# mother_card_14.net
KiCad netlist of a schematic drawn in EAGLE
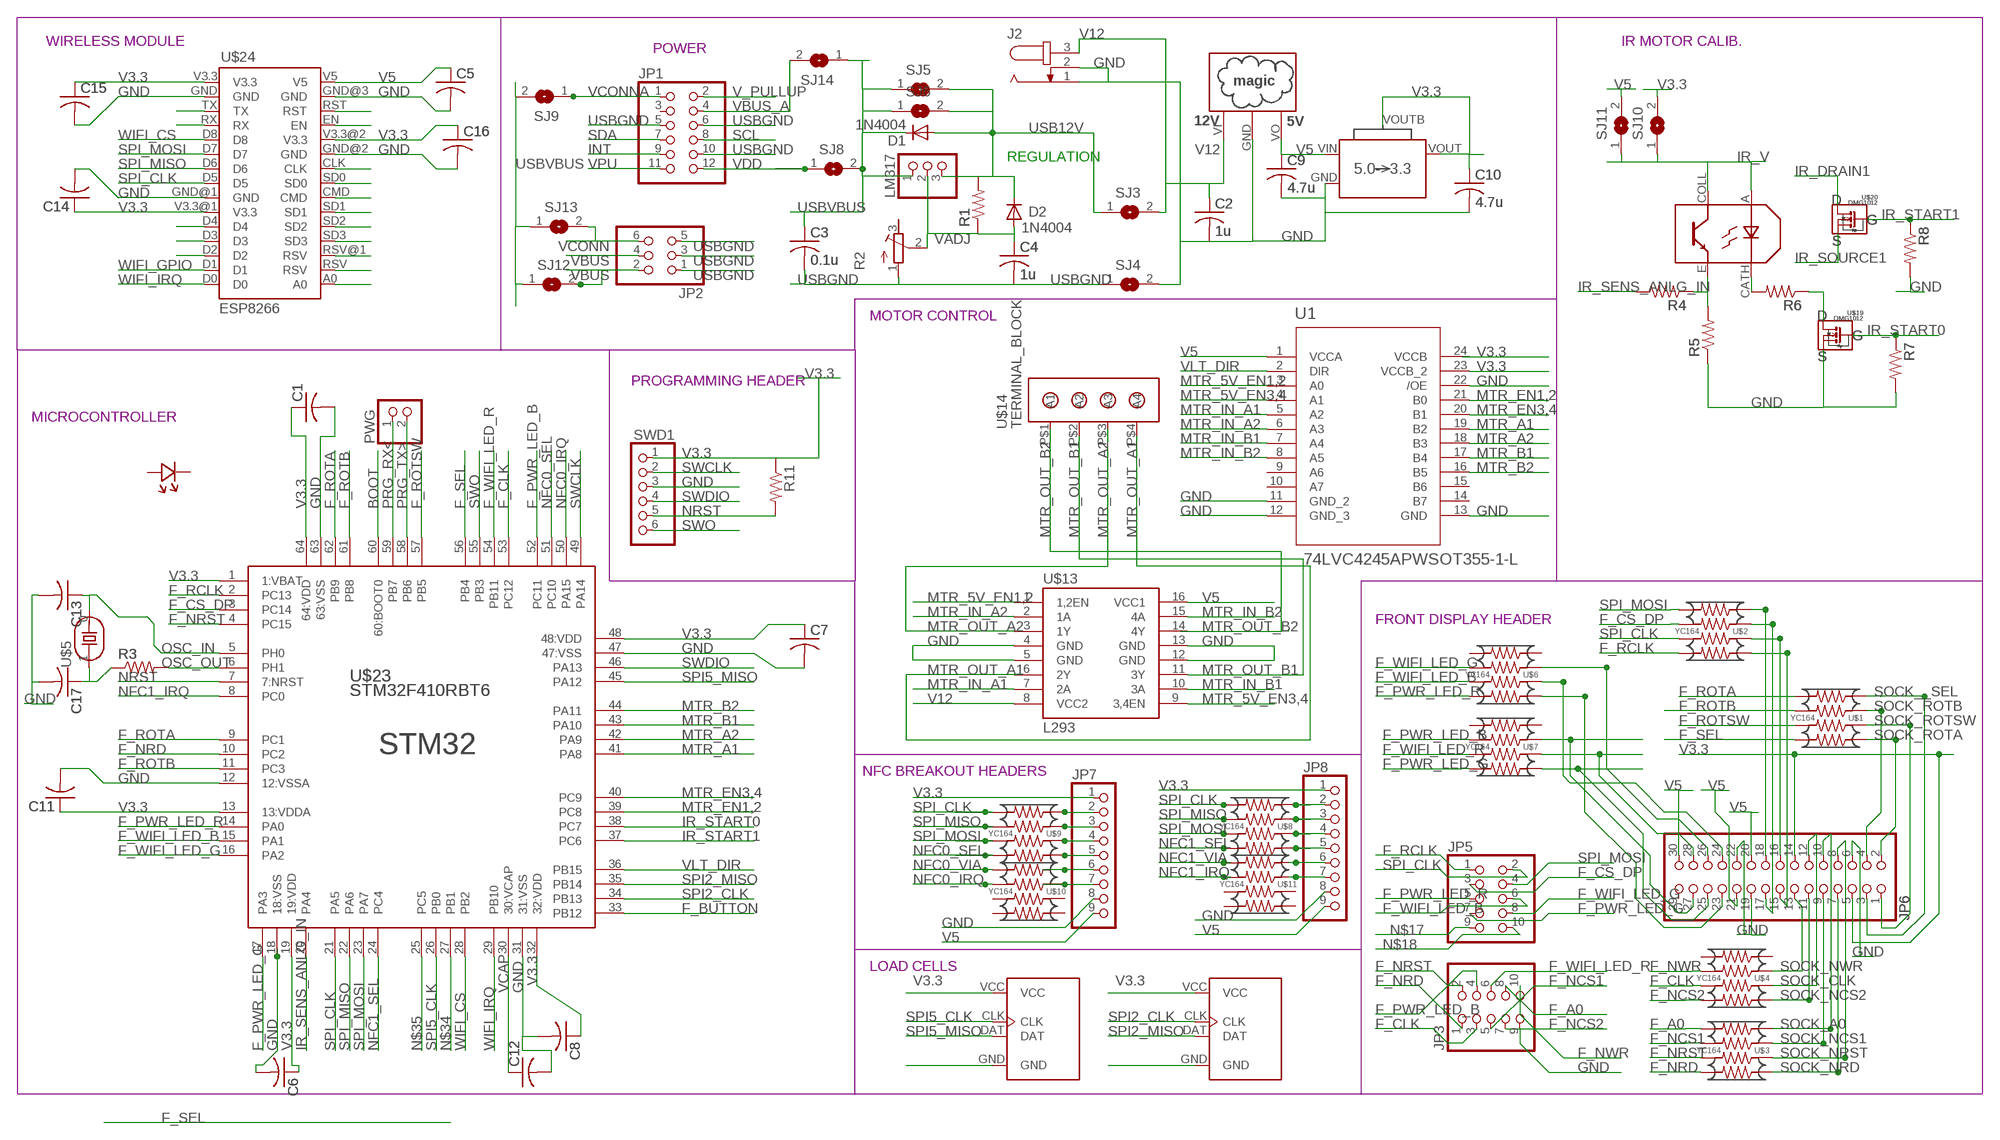
[diagram p0: schematic, sheet 1]

(export (version "E")
  (design (tool "Eeschema 10.0.6"))
  (components
    (comp (ref "C1")
      (value "C-USC0805")
      (footprint "eagle-import:C0805")
      (libsource (lib "eagle-import") (part "C-USC0805"))
    )
    (comp (ref "C2")
      (value "1u")
      (footprint "eagle-import:C0805")
      (libsource (lib "eagle-import") (part "C-USC0805"))
    )
    (comp (ref "C3")
      (value "0.1u")
      (footprint "eagle-import:C0805")
      (libsource (lib "eagle-import") (part "C-USC0805"))
    )
    (comp (ref "C4")
      (value "1u")
      (footprint "eagle-import:C0805")
      (libsource (lib "eagle-import") (part "C-USC0805"))
    )
    (comp (ref "C5")
      (value "C-USC0805")
      (footprint "eagle-import:C0805")
      (libsource (lib "eagle-import") (part "C-USC0805"))
    )
    (comp (ref "C6")
      (value "C-USC0805")
      (footprint "eagle-import:C0805")
      (libsource (lib "eagle-import") (part "C-USC0805"))
    )
    (comp (ref "C7")
      (value "C-USC0805")
      (footprint "eagle-import:C0805")
      (libsource (lib "eagle-import") (part "C-USC0805"))
    )
    (comp (ref "C8")
      (value "C-USC0805")
      (footprint "eagle-import:C0805")
      (libsource (lib "eagle-import") (part "C-USC0805"))
    )
    (comp (ref "C9")
      (value "4.7u")
      (footprint "eagle-import:C0805")
      (libsource (lib "eagle-import") (part "C-USC0805"))
    )
    (comp (ref "C10")
      (value "4.7u")
      (footprint "eagle-import:C0805")
      (libsource (lib "eagle-import") (part "C-USC0805"))
    )
    (comp (ref "C11")
      (value "C-USC0805")
      (footprint "eagle-import:C0805")
      (libsource (lib "eagle-import") (part "C-USC0805"))
    )
    (comp (ref "C12")
      (value "C-USC0805")
      (footprint "eagle-import:C0805")
      (libsource (lib "eagle-import") (part "C-USC0805"))
    )
    (comp (ref "C13")
      (value "C-USC0603")
      (footprint "eagle-import:C0603")
      (libsource (lib "eagle-import") (part "C-USC0603"))
    )
    (comp (ref "C14")
      (value "C-USC0805")
      (footprint "eagle-import:C0805")
      (libsource (lib "eagle-import") (part "C-USC0805"))
    )
    (comp (ref "C15")
      (value "C-USC0805")
      (footprint "eagle-import:C0805")
      (libsource (lib "eagle-import") (part "C-USC0805"))
    )
    (comp (ref "C16")
      (value "C-USC0805")
      (footprint "eagle-import:C0805")
      (libsource (lib "eagle-import") (part "C-USC0805"))
    )
    (comp (ref "C17")
      (value "C-USC0603")
      (footprint "eagle-import:C0603")
      (libsource (lib "eagle-import") (part "C-USC0603"))
    )
    (comp (ref "D1")
      (value "1N4004")
      (footprint "eagle-import:DO41-10")
      (libsource (lib "eagle-import") (part "1N4004"))
    )
    (comp (ref "D2")
      (value "1N4004")
      (footprint "eagle-import:DO41-10")
      (libsource (lib "eagle-import") (part "1N4004"))
    )
    (comp (ref "J2")
      (value "JACK-PLUG0")
      (footprint "eagle-import:SPC4077")
      (libsource (lib "eagle-import") (part "JACK-PLUG0"))
    )
    (comp (ref "JP1")
      (value "PINHD-2X6")
      (footprint "eagle-import:2X06")
      (libsource (lib "eagle-import") (part "PINHD-2X6"))
    )
    (comp (ref "JP2")
      (value "PINHD-2X3")
      (footprint "eagle-import:2X03")
      (libsource (lib "eagle-import") (part "PINHD-2X3"))
    )
    (comp (ref "JP3")
      (value "PINHD-2X5")
      (footprint "eagle-import:2X05")
      (libsource (lib "eagle-import") (part "PINHD-2X5"))
    )
    (comp (ref "JP5")
      (value "PINHD-2X5")
      (footprint "eagle-import:2X05")
      (libsource (lib "eagle-import") (part "PINHD-2X5"))
    )
    (comp (ref "JP6")
      (value "PINHD-2X15/SOCK")
      (footprint "eagle-import:2X15_SOCK")
      (libsource (lib "eagle-import") (part "PINHD-2X15/SOCK"))
    )
    (comp (ref "JP7")
      (value "PINHD-1X9/90")
      (footprint "eagle-import:1X09_90")
      (libsource (lib "eagle-import") (part "PINHD-1X9/90"))
    )
    (comp (ref "JP8")
      (value "PINHD-1X9/90")
      (footprint "eagle-import:1X09_90")
      (libsource (lib "eagle-import") (part "PINHD-1X9/90"))
    )
    (comp (ref "LM317")
      (value "PINHD-1X3")
      (footprint "eagle-import:1X03")
      (libsource (lib "eagle-import") (part "PINHD-1X3"))
    )
    (comp (ref "PWG")
      (value "PINHD-1X2")
      (footprint "eagle-import:1X02")
      (libsource (lib "eagle-import") (part "PINHD-1X2"))
    )
    (comp (ref "R1")
      (value "R-US_R0805")
      (footprint "eagle-import:R0805")
      (libsource (lib "eagle-import") (part "seniorDesign_R-US_R0805"))
    )
    (comp (ref "R2")
      (value "R-TRIMM64W")
      (footprint "eagle-import:RTRIM64W")
      (libsource (lib "eagle-import") (part "R-TRIMM64W"))
    )
    (comp (ref "R3")
      (value "R-US_R0805")
      (footprint "eagle-import:R0805")
      (libsource (lib "eagle-import") (part "seniorDesign_R-US_R0805"))
    )
    (comp (ref "R4")
      (value "R-US_R0805")
      (footprint "eagle-import:R0805")
      (libsource (lib "eagle-import") (part "seniorDesign_R-US_R0805"))
    )
    (comp (ref "R5")
      (value "R-US_R0805")
      (footprint "eagle-import:R0805")
      (libsource (lib "eagle-import") (part "seniorDesign_R-US_R0805"))
    )
    (comp (ref "R6")
      (value "R-US_R0805")
      (footprint "eagle-import:R0805")
      (libsource (lib "eagle-import") (part "seniorDesign_R-US_R0805"))
    )
    (comp (ref "R7")
      (value "R-US_R0805")
      (footprint "eagle-import:R0805")
      (libsource (lib "eagle-import") (part "seniorDesign_R-US_R0805"))
    )
    (comp (ref "R8")
      (value "R-US_R0805")
      (footprint "eagle-import:R0805")
      (libsource (lib "eagle-import") (part "seniorDesign_R-US_R0805"))
    )
    (comp (ref "R11")
      (value "R-US_R0805")
      (footprint "eagle-import:R0805")
      (libsource (lib "eagle-import") (part "R-US_R0805"))
    )
    (comp (ref "SJ3") (value "SJ") (footprint "eagle-import:SJ") (libsource (lib "eagle-import") (part "SJ")))
    (comp (ref "SJ4") (value "SJ") (footprint "eagle-import:SJ") (libsource (lib "eagle-import") (part "SJ")))
    (comp (ref "SJ5") (value "SJ") (footprint "eagle-import:SJ") (libsource (lib "eagle-import") (part "SJ")))
    (comp (ref "SJ6") (value "SJ") (footprint "eagle-import:SJ") (libsource (lib "eagle-import") (part "SJ")))
    (comp (ref "SJ8") (value "SJ") (footprint "eagle-import:SJ") (libsource (lib "eagle-import") (part "SJ")))
    (comp (ref "SJ9") (value "SJ") (footprint "eagle-import:SJ") (libsource (lib "eagle-import") (part "SJ")))
    (comp (ref "SJ10")
      (value "SJ")
      (footprint "eagle-import:SJ")
      (libsource (lib "eagle-import") (part "SJ"))
    )
    (comp (ref "SJ11")
      (value "SJ")
      (footprint "eagle-import:SJ")
      (libsource (lib "eagle-import") (part "SJ"))
    )
    (comp (ref "SJ12")
      (value "SJ")
      (footprint "eagle-import:SJ")
      (libsource (lib "eagle-import") (part "SJ"))
    )
    (comp (ref "SJ13")
      (value "SJ")
      (footprint "eagle-import:SJ")
      (libsource (lib "eagle-import") (part "SJ"))
    )
    (comp (ref "SJ14")
      (value "SJ")
      (footprint "eagle-import:SJ")
      (libsource (lib "eagle-import") (part "SJ"))
    )
    (comp (ref "SWD1")
      (value "PINHD-1X6")
      (footprint "eagle-import:1X06")
      (libsource (lib "eagle-import") (part "PINHD-1X6"))
    )
    (comp (ref "U$1")
      (value "YC164")
      (footprint "eagle-import:YC164")
      (libsource (lib "eagle-import") (part "YC164"))
    )
    (comp (ref "U$2")
      (value "YC164")
      (footprint "eagle-import:YC164")
      (libsource (lib "eagle-import") (part "YC164"))
    )
    (comp (ref "U$3")
      (value "YC164")
      (footprint "eagle-import:YC164")
      (libsource (lib "eagle-import") (part "YC164"))
    )
    (comp (ref "U$4")
      (value "YC164")
      (footprint "eagle-import:YC164")
      (libsource (lib "eagle-import") (part "YC164"))
    )
    (comp (ref "U$5")
      (value "HC-49S_9B")
      (footprint "eagle-import:HC-49S_9B")
      (libsource (lib "eagle-import") (part "HC-49S_9B"))
    )
    (comp (ref "U$6")
      (value "YC164")
      (footprint "eagle-import:YC164")
      (libsource (lib "eagle-import") (part "YC164"))
    )
    (comp (ref "U$7")
      (value "YC164")
      (footprint "eagle-import:YC164")
      (libsource (lib "eagle-import") (part "YC164"))
    )
    (comp (ref "U$8")
      (value "YC164")
      (footprint "eagle-import:YC164")
      (libsource (lib "eagle-import") (part "YC164"))
    )
    (comp (ref "U$9")
      (value "YC164")
      (footprint "eagle-import:YC164")
      (libsource (lib "eagle-import") (part "YC164"))
    )
    (comp (ref "U$10")
      (value "YC164")
      (footprint "eagle-import:YC164")
      (libsource (lib "eagle-import") (part "YC164"))
    )
    (comp (ref "U$11")
      (value "YC164")
      (footprint "eagle-import:YC164")
      (libsource (lib "eagle-import") (part "YC164"))
    )
    (comp (ref "U$12")
      (value "LED0603")
      (footprint "eagle-import:LED")
      (libsource (lib "eagle-import") (part "LED0603"))
    )
    (comp (ref "U$13")
      (value "L293")
      (footprint "eagle-import:DIL16")
      (libsource (lib "eagle-import") (part "L293"))
    )
    (comp (ref "U$14")
      (value "TERMINAL_BLOCK")
      (footprint "eagle-import:1X4_BLOCK")
      (libsource (lib "eagle-import") (part "TERMINAL_BLOCK"))
    )
    (comp (ref "U$15")
      (value "AP2114H")
      (footprint "eagle-import:AP2114H")
      (libsource (lib "eagle-import") (part "AP2114H"))
    )
    (comp (ref "U$16")
      (value "OKI-78SR-W36")
      (footprint "eagle-import:SIP3")
      (libsource (lib "eagle-import") (part "OKI-78SR-W36"))
    )
    (comp (ref "U$18")
      (value "TCRT5000")
      (footprint "eagle-import:TCRT5000")
      (libsource (lib "eagle-import") (part "TCRT5000"))
    )
    (comp (ref "U$19")
      (value "DMG1012")
      (footprint "eagle-import:SOT323")
      (libsource (lib "eagle-import") (part "DMG1012"))
    )
    (comp (ref "U$20")
      (value "DMG1012")
      (footprint "eagle-import:SOT323")
      (libsource (lib "eagle-import") (part "DMG1012"))
    )
    (comp (ref "U$21")
      (value "HX711")
      (footprint "eagle-import:HX711")
      (libsource (lib "eagle-import") (part "HX711"))
    )
    (comp (ref "U$22")
      (value "HX711")
      (footprint "eagle-import:HX711")
      (libsource (lib "eagle-import") (part "HX711"))
    )
    (comp (ref "U$23")
      (value "STM32F410RBT6")
      (footprint "eagle-import:QFP50P1200X1200X160-64N")
      (libsource (lib "eagle-import") (part "STM32F410RBT6"))
    )
    (comp (ref "U$24")
      (value "ESP8266")
      (footprint "eagle-import:ESP8266")
      (libsource (lib "eagle-import") (part "ESP8266"))
    )
    (comp (ref "U1")
      (value "74LVC4245APWSOT355-1-L")
      (footprint "eagle-import:SOT355-1-L")
      (fields (field (name "MANUFACTURER_PART_NUMBER") "74LVC4245APW"))
      (libsource (lib "eagle-import") (part "74LVC4245APWSOT355-1-L"))
    )
  )
  (nets
    (net (code "1") (name "/BOOT") (class "Default")
      (node (ref "U$23") (pin "60") (pinfunction "60:BOOT0_60") (pintype "bidirectional"))
    )
    (net (code "2") (name "/F_A0") (class "Default")
      (node (ref "JP3") (pin "8") (pinfunction "8_8") (pintype "passive"))
      (node (ref "U$3") (pin "P$4") (pinfunction "4_P$4") (pintype "passive"))
    )
    (net (code "3") (name "/F_BUTTON") (class "Default")
      (node (ref "U$23") (pin "33") (pinfunction "PB12_33") (pintype "bidirectional"))
    )
    (net (code "4") (name "/F_CLK") (class "Default")
      (node (ref "JP3") (pin "3") (pinfunction "3_3") (pintype "passive"))
      (node (ref "U$23") (pin "53") (pinfunction "PC12_53") (pintype "bidirectional"))
      (node (ref "U$4") (pin "P$2") (pinfunction "2_P$2") (pintype "passive"))
    )
    (net (code "5") (name "/F_CS_DP") (class "Default")
      (node (ref "JP5") (pin "3") (pinfunction "3_3") (pintype "passive"))
      (node (ref "U$2") (pin "P$3") (pinfunction "3_P$3") (pintype "passive"))
      (node (ref "U$23") (pin "3") (pinfunction "PC14_3") (pintype "bidirectional"))
    )
    (net (code "6") (name "/F_NCS1") (class "Default")
      (node (ref "JP3") (pin "5") (pinfunction "5_5") (pintype "passive"))
      (node (ref "U$3") (pin "P$3") (pinfunction "3_P$3") (pintype "passive"))
    )
    (net (code "7") (name "/F_NCS2") (class "Default")
      (node (ref "JP3") (pin "7") (pinfunction "7_7") (pintype "passive"))
      (node (ref "U$4") (pin "P$1") (pinfunction "1_P$1") (pintype "passive"))
    )
    (net (code "8") (name "/F_NRD") (class "Default")
      (node (ref "JP3") (pin "1") (pinfunction "1_1") (pintype "passive"))
      (node (ref "U$23") (pin "10") (pinfunction "PC2_10") (pintype "bidirectional"))
      (node (ref "U$3") (pin "P$1") (pinfunction "1_P$1") (pintype "passive"))
    )
    (net (code "9") (name "/F_NRST") (class "Default")
      (node (ref "JP3") (pin "2") (pinfunction "2_2") (pintype "passive"))
      (node (ref "U$23") (pin "4") (pinfunction "PC15_4") (pintype "bidirectional"))
      (node (ref "U$3") (pin "P$2") (pinfunction "2_P$2") (pintype "passive"))
    )
    (net (code "10") (name "/F_NWR") (class "Default")
      (node (ref "JP3") (pin "10") (pinfunction "10_10") (pintype "passive"))
      (node (ref "U$4") (pin "P$3") (pinfunction "3_P$3") (pintype "passive"))
    )
    (net (code "11") (name "/F_PWR_LED_B") (class "Default")
      (node (ref "JP3") (pin "4") (pinfunction "4_4") (pintype "passive"))
      (node (ref "U$23") (pin "52") (pinfunction "PC11_52") (pintype "bidirectional"))
      (node (ref "U$7") (pin "P$3") (pinfunction "3_P$3") (pintype "passive"))
    )
    (net (code "12") (name "/F_PWR_LED_G") (class "Default")
      (node (ref "JP5") (pin "7") (pinfunction "7_7") (pintype "passive"))
      (node (ref "U$23") (pin "17") (pinfunction "PA3_17") (pintype "bidirectional"))
      (node (ref "U$7") (pin "P$1") (pinfunction "1_P$1") (pintype "passive"))
    )
    (net (code "13") (name "/F_PWR_LED_R") (class "Default")
      (node (ref "JP5") (pin "5") (pinfunction "5_5") (pintype "passive"))
      (node (ref "U$23") (pin "14") (pinfunction "PA0_14") (pintype "bidirectional"))
      (node (ref "U$6") (pin "P$1") (pinfunction "1_P$1") (pintype "passive"))
    )
    (net (code "14") (name "/F_RCLK") (class "Default")
      (node (ref "JP5") (pin "1") (pinfunction "1_1") (pintype "passive"))
      (node (ref "U$2") (pin "P$1") (pinfunction "1_P$1") (pintype "passive"))
      (node (ref "U$23") (pin "2") (pinfunction "PC13_2") (pintype "bidirectional"))
    )
    (net (code "15") (name "/F_ROTA") (class "Default")
      (node (ref "U$1") (pin "P$4") (pinfunction "4_P$4") (pintype "passive"))
      (node (ref "U$23") (pin "62") (pinfunction "PB9_62") (pintype "bidirectional"))
      (node (ref "U$23") (pin "9") (pinfunction "PC1_9") (pintype "bidirectional"))
    )
    (net (code "16") (name "/F_ROTB") (class "Default")
      (node (ref "U$1") (pin "P$3") (pinfunction "3_P$3") (pintype "passive"))
      (node (ref "U$23") (pin "11") (pinfunction "PC3_11") (pintype "bidirectional"))
      (node (ref "U$23") (pin "61") (pinfunction "PB8_61") (pintype "bidirectional"))
    )
    (net (code "17") (name "/F_ROTSW") (class "Default")
      (node (ref "U$1") (pin "P$2") (pinfunction "2_P$2") (pintype "passive"))
      (node (ref "U$23") (pin "57") (pinfunction "PB5_57") (pintype "bidirectional"))
    )
    (net (code "18") (name "/F_SEL") (class "Default")
      (node (ref "U$1") (pin "P$1") (pinfunction "1_P$1") (pintype "passive"))
      (node (ref "U$23") (pin "56") (pinfunction "PB4_56") (pintype "bidirectional"))
    )
    (net (code "19") (name "/F_WIFI_LED_B") (class "Default")
      (node (ref "JP5") (pin "6") (pinfunction "6_6") (pintype "passive"))
      (node (ref "U$23") (pin "15") (pinfunction "PA1_15") (pintype "bidirectional"))
      (node (ref "U$6") (pin "P$2") (pinfunction "2_P$2") (pintype "passive"))
    )
    (net (code "20") (name "/F_WIFI_LED_G") (class "Default")
      (node (ref "JP5") (pin "8") (pinfunction "8_8") (pintype "passive"))
      (node (ref "U$23") (pin "16") (pinfunction "PA2_16") (pintype "bidirectional"))
      (node (ref "U$6") (pin "P$3") (pinfunction "3_P$3") (pintype "passive"))
    )
    (net (code "21") (name "/F_WIFI_LED_R") (class "Default")
      (node (ref "JP3") (pin "6") (pinfunction "6_6") (pintype "passive"))
      (node (ref "U$23") (pin "54") (pinfunction "PB11_54") (pintype "bidirectional"))
      (node (ref "U$7") (pin "P$2") (pinfunction "2_P$2") (pintype "passive"))
    )
    (net (code "22") (name "/GND") (class "Default")
      (node (ref "C1") (pin "2") (pinfunction "2_2") (pintype "passive"))
      (node (ref "C10") (pin "2") (pinfunction "2_2") (pintype "passive"))
      (node (ref "C11") (pin "2") (pinfunction "2_2") (pintype "passive"))
      (node (ref "C12") (pin "2") (pinfunction "2_2") (pintype "passive"))
      (node (ref "C13") (pin "2") (pinfunction "2_2") (pintype "passive"))
      (node (ref "C14") (pin "2") (pinfunction "2_2") (pintype "passive"))
      (node (ref "C15") (pin "2") (pinfunction "2_2") (pintype "passive"))
      (node (ref "C16") (pin "2") (pinfunction "2_2") (pintype "passive"))
      (node (ref "C17") (pin "2") (pinfunction "2_2") (pintype "passive"))
      (node (ref "C2") (pin "2") (pinfunction "2_2") (pintype "passive"))
      (node (ref "C5") (pin "2") (pinfunction "2_2") (pintype "passive"))
      (node (ref "C6") (pin "2") (pinfunction "2_2") (pintype "passive"))
      (node (ref "C7") (pin "2") (pinfunction "2_2") (pintype "passive"))
      (node (ref "C8") (pin "2") (pinfunction "2_2") (pintype "passive"))
      (node (ref "C9") (pin "2") (pinfunction "2_2") (pintype "passive"))
      (node (ref "J2") (pin "1") (pinfunction "1_1") (pintype "passive"))
      (node (ref "J2") (pin "2") (pinfunction "2_2") (pintype "passive"))
      (node (ref "JP3") (pin "9") (pinfunction "9_9") (pintype "passive"))
      (node (ref "JP6") (pin "19") (pinfunction "19_19") (pintype "passive"))
      (node (ref "JP6") (pin "22") (pinfunction "22_22") (pintype "passive"))
      (node (ref "JP6") (pin "6") (pinfunction "6_6") (pintype "passive"))
      (node (ref "JP7") (pin "8") (pinfunction "8_8") (pintype "passive"))
      (node (ref "JP8") (pin "8") (pinfunction "8_8") (pintype "passive"))
      (node (ref "R5") (pin "1") (pinfunction "1_1") (pintype "passive"))
      (node (ref "R7") (pin "2") (pinfunction "2_2") (pintype "passive"))
      (node (ref "R8") (pin "2") (pinfunction "2_2") (pintype "passive"))
      (node (ref "SJ4") (pin "2") (pinfunction "2_2") (pintype "passive"))
      (node (ref "SWD1") (pin "3") (pinfunction "3_3") (pintype "passive"))
      (node (ref "U$13") (pin "12") (pinfunction "GND_12") (pintype "bidirectional"))
      (node (ref "U$13") (pin "13") (pinfunction "GND_13") (pintype "bidirectional"))
      (node (ref "U$13") (pin "4") (pinfunction "GND_4") (pintype "bidirectional"))
      (node (ref "U$13") (pin "5") (pinfunction "GND_5") (pintype "bidirectional"))
      (node (ref "U$15") (pin "GND") (pinfunction "GND_GND") (pintype "power_in"))
      (node (ref "U$16") (pin "GND") (pinfunction "P$2_GND") (pintype "power_in"))
      (node (ref "U$19") (pin "S") (pinfunction "S_S") (pintype "bidirectional"))
      (node (ref "U$21") (pin "GND") (pinfunction "GND_GND") (pintype "power_in"))
      (node (ref "U$22") (pin "GND") (pinfunction "GND_GND") (pintype "power_in"))
      (node (ref "U$23") (pin "12") (pinfunction "12:VSSA_12") (pintype "bidirectional"))
      (node (ref "U$23") (pin "18") (pinfunction "18:VSS_18") (pintype "bidirectional"))
      (node (ref "U$23") (pin "31") (pinfunction "31:VSS_31") (pintype "bidirectional"))
      (node (ref "U$23") (pin "47") (pinfunction "47:VSS_47") (pintype "bidirectional"))
      (node (ref "U$23") (pin "63") (pinfunction "63:VSS_63") (pintype "bidirectional"))
      (node (ref "U$24") (pin "GND") (pinfunction "GND_GND") (pintype "bidirectional"))
      (node (ref "U$24") (pin "GND@1") (pinfunction "GND_GND@1") (pintype "bidirectional"))
      (node (ref "U$24") (pin "GND@2") (pinfunction "GND_GND@2") (pintype "bidirectional"))
      (node (ref "U$24") (pin "GND@3") (pinfunction "GND_GND@3") (pintype "bidirectional"))
      (node (ref "U1") (pin "11") (pinfunction "GND_2_11") (pintype "power_in"))
      (node (ref "U1") (pin "12") (pinfunction "GND_3_12") (pintype "power_in"))
      (node (ref "U1") (pin "13") (pinfunction "GND_13") (pintype "power_in"))
      (node (ref "U1") (pin "22") (pinfunction "/OE_22") (pintype "input"))
    )
    (net (code "23") (name "/INT") (class "Default")
      (node (ref "JP1") (pin "9") (pinfunction "9_9") (pintype "passive"))
    )
    (net (code "24") (name "/IR_DRAIN1") (class "Default")
      (node (ref "U$20") (pin "D") (pinfunction "D_D") (pintype "bidirectional"))
    )
    (net (code "25") (name "/IR_SENS_ANLG_IN") (class "Default")
      (node (ref "R4") (pin "2") (pinfunction "2_2") (pintype "passive"))
      (node (ref "U$23") (pin "20") (pinfunction "PA4_20") (pintype "bidirectional"))
    )
    (net (code "26") (name "/IR_SOURCE1") (class "Default")
      (node (ref "U$20") (pin "S") (pinfunction "S_S") (pintype "bidirectional"))
    )
    (net (code "27") (name "/IR_START0") (class "Default")
      (node (ref "R7") (pin "1") (pinfunction "1_1") (pintype "passive"))
      (node (ref "U$19") (pin "G") (pinfunction "G_G") (pintype "bidirectional"))
      (node (ref "U$23") (pin "38") (pinfunction "PC7_38") (pintype "bidirectional"))
    )
    (net (code "28") (name "/IR_START1") (class "Default")
      (node (ref "R8") (pin "1") (pinfunction "1_1") (pintype "passive"))
      (node (ref "U$20") (pin "G") (pinfunction "G_G") (pintype "bidirectional"))
      (node (ref "U$23") (pin "37") (pinfunction "PC6_37") (pintype "bidirectional"))
    )
    (net (code "29") (name "/IR_V") (class "Default")
      (node (ref "SJ10") (pin "1") (pinfunction "1_1") (pintype "passive"))
      (node (ref "SJ11") (pin "1") (pinfunction "1_1") (pintype "passive"))
      (node (ref "U$18") (pin "A") (pinfunction "A_A") (pintype "bidirectional"))
      (node (ref "U$18") (pin "COLL") (pinfunction "COLL_COLL") (pintype "bidirectional"))
    )
    (net (code "30") (name "/MTR_5V_EN1,2") (class "Default")
      (node (ref "U$13") (pin "1") (pinfunction "1,2EN_1") (pintype "bidirectional"))
      (node (ref "U1") (pin "3") (pinfunction "A0_3") (pintype "bidirectional"))
    )
    (net (code "31") (name "/MTR_5V_EN3,4") (class "Default")
      (node (ref "U$13") (pin "9") (pinfunction "3,4EN_9") (pintype "bidirectional"))
      (node (ref "U1") (pin "4") (pinfunction "A1_4") (pintype "bidirectional"))
    )
    (net (code "32") (name "/MTR_A1") (class "Default")
      (node (ref "U$23") (pin "41") (pinfunction "PA8_41") (pintype "bidirectional"))
      (node (ref "U1") (pin "19") (pinfunction "B2_19") (pintype "bidirectional"))
    )
    (net (code "33") (name "/MTR_A2") (class "Default")
      (node (ref "U$23") (pin "42") (pinfunction "PA9_42") (pintype "bidirectional"))
      (node (ref "U1") (pin "18") (pinfunction "B3_18") (pintype "bidirectional"))
    )
    (net (code "34") (name "/MTR_B1") (class "Default")
      (node (ref "U$23") (pin "43") (pinfunction "PA10_43") (pintype "bidirectional"))
      (node (ref "U1") (pin "17") (pinfunction "B4_17") (pintype "bidirectional"))
    )
    (net (code "35") (name "/MTR_B2") (class "Default")
      (node (ref "U$23") (pin "44") (pinfunction "PA11_44") (pintype "bidirectional"))
      (node (ref "U1") (pin "16") (pinfunction "B5_16") (pintype "bidirectional"))
    )
    (net (code "36") (name "/MTR_EN1,2") (class "Default")
      (node (ref "U$23") (pin "39") (pinfunction "PC8_39") (pintype "bidirectional"))
      (node (ref "U1") (pin "21") (pinfunction "B0_21") (pintype "bidirectional"))
    )
    (net (code "37") (name "/MTR_EN3,4") (class "Default")
      (node (ref "U$23") (pin "40") (pinfunction "PC9_40") (pintype "bidirectional"))
      (node (ref "U1") (pin "20") (pinfunction "B1_20") (pintype "bidirectional"))
    )
    (net (code "38") (name "/MTR_IN_A1") (class "Default")
      (node (ref "U$13") (pin "7") (pinfunction "2A_7") (pintype "bidirectional"))
      (node (ref "U1") (pin "5") (pinfunction "A2_5") (pintype "bidirectional"))
    )
    (net (code "39") (name "/MTR_IN_A2") (class "Default")
      (node (ref "U$13") (pin "2") (pinfunction "1A_2") (pintype "bidirectional"))
      (node (ref "U1") (pin "6") (pinfunction "A3_6") (pintype "bidirectional"))
    )
    (net (code "40") (name "/MTR_IN_B1") (class "Default")
      (node (ref "U$13") (pin "10") (pinfunction "3A_10") (pintype "bidirectional"))
      (node (ref "U1") (pin "7") (pinfunction "A4_7") (pintype "bidirectional"))
    )
    (net (code "41") (name "/MTR_IN_B2") (class "Default")
      (node (ref "U$13") (pin "15") (pinfunction "4A_15") (pintype "bidirectional"))
      (node (ref "U1") (pin "8") (pinfunction "A5_8") (pintype "bidirectional"))
    )
    (net (code "42") (name "/MTR_OUT_A1") (class "Default")
      (node (ref "U$13") (pin "6") (pinfunction "2Y_6") (pintype "bidirectional"))
      (node (ref "U$14") (pin "P$4") (pinfunction "A4_P$4") (pintype "bidirectional"))
    )
    (net (code "43") (name "/MTR_OUT_A2") (class "Default")
      (node (ref "U$13") (pin "3") (pinfunction "1Y_3") (pintype "bidirectional"))
      (node (ref "U$14") (pin "P$3") (pinfunction "A3_P$3") (pintype "bidirectional"))
    )
    (net (code "44") (name "/MTR_OUT_B1") (class "Default")
      (node (ref "U$13") (pin "11") (pinfunction "3Y_11") (pintype "bidirectional"))
      (node (ref "U$14") (pin "P$2") (pinfunction "A2_P$2") (pintype "bidirectional"))
    )
    (net (code "45") (name "/MTR_OUT_B2") (class "Default")
      (node (ref "U$13") (pin "14") (pinfunction "4Y_14") (pintype "bidirectional"))
      (node (ref "U$14") (pin "P$1") (pinfunction "A1_P$1") (pintype "bidirectional"))
    )
    (net (code "46") (name "/N$17") (class "Default")
      (node (ref "JP5") (pin "9") (pinfunction "9_9") (pintype "passive"))
    )
    (net (code "47") (name "/N$18") (class "Default")
      (node (ref "JP5") (pin "10") (pinfunction "10_10") (pintype "passive"))
    )
    (net (code "48") (name "/N$34") (class "Default")
      (node (ref "U$23") (pin "27") (pinfunction "PB1_27") (pintype "bidirectional"))
    )
    (net (code "49") (name "/N$35") (class "Default")
      (node (ref "U$23") (pin "25") (pinfunction "PC5_25") (pintype "bidirectional"))
    )
    (net (code "50") (name "/NFC0_IRQ") (class "Default")
      (node (ref "U$10") (pin "P$3") (pinfunction "3_P$3") (pintype "passive"))
      (node (ref "U$23") (pin "50") (pinfunction "PA15_50") (pintype "bidirectional"))
    )
    (net (code "51") (name "/NFC0_SEL") (class "Default")
      (node (ref "U$23") (pin "51") (pinfunction "PC10_51") (pintype "bidirectional"))
      (node (ref "U$9") (pin "P$1") (pinfunction "1_P$1") (pintype "passive"))
    )
    (net (code "52") (name "/NFC0_VIA") (class "Default")
      (node (ref "U$10") (pin "P$4") (pinfunction "4_P$4") (pintype "passive"))
    )
    (net (code "53") (name "/NFC1_IRQ") (class "Default")
      (node (ref "U$11") (pin "P$3") (pinfunction "3_P$3") (pintype "passive"))
      (node (ref "U$23") (pin "8") (pinfunction "PC0_8") (pintype "bidirectional"))
    )
    (net (code "54") (name "/NFC1_SEL") (class "Default")
      (node (ref "U$23") (pin "24") (pinfunction "PC4_24") (pintype "bidirectional"))
      (node (ref "U$8") (pin "P$1") (pinfunction "1_P$1") (pintype "passive"))
    )
    (net (code "55") (name "/NFC1_VIA") (class "Default")
      (node (ref "U$11") (pin "P$4") (pinfunction "4_P$4") (pintype "passive"))
    )
    (net (code "56") (name "/NRST") (class "Default")
      (node (ref "R11") (pin "2") (pinfunction "2_2") (pintype "passive"))
      (node (ref "SWD1") (pin "5") (pinfunction "5_5") (pintype "passive"))
      (node (ref "U$23") (pin "7") (pinfunction "7:NRST_7") (pintype "bidirectional"))
    )
    (net (code "57") (name "/OSC_IN") (class "Default")
      (node (ref "C13") (pin "1") (pinfunction "1_1") (pintype "passive"))
      (node (ref "U$23") (pin "5") (pinfunction "PH0_5") (pintype "bidirectional"))
      (node (ref "U$5") (pin "0") (pinfunction "P$1_0") (pintype "bidirectional"))
    )
    (net (code "58") (name "/OSC_OUT") (class "Default")
      (node (ref "C17") (pin "1") (pinfunction "1_1") (pintype "passive"))
      (node (ref "R3") (pin "1") (pinfunction "1_1") (pintype "passive"))
      (node (ref "U$5") (pin "1") (pinfunction "P$2_1") (pintype "bidirectional"))
    )
    (net (code "59") (name "/PRG_RX<") (class "Default")
      (node (ref "PWG") (pin "1") (pinfunction "1_1") (pintype "passive"))
      (node (ref "U$23") (pin "59") (pinfunction "PB7_59") (pintype "bidirectional"))
    )
    (net (code "60") (name "/PRG_TX>") (class "Default")
      (node (ref "PWG") (pin "2") (pinfunction "2_2") (pintype "passive"))
      (node (ref "U$23") (pin "58") (pinfunction "PB6_58") (pintype "bidirectional"))
    )
    (net (code "61") (name "/SCL") (class "Default")
      (node (ref "JP1") (pin "8") (pinfunction "8_8") (pintype "passive"))
    )
    (net (code "62") (name "/SDA") (class "Default")
      (node (ref "JP1") (pin "7") (pinfunction "7_7") (pintype "passive"))
    )
    (net (code "63") (name "/SOCK_A0") (class "Default")
      (node (ref "JP6") (pin "10") (pinfunction "10_10") (pintype "passive"))
      (node (ref "U$3") (pin "P$44") (pinfunction "44_P$44") (pintype "passive"))
    )
    (net (code "64") (name "/SOCK_CLK") (class "Default")
      (node (ref "JP6") (pin "12") (pinfunction "12_12") (pintype "passive"))
      (node (ref "U$4") (pin "P$22") (pinfunction "22_P$22") (pintype "passive"))
    )
    (net (code "65") (name "/SOCK_NCS1") (class "Default")
      (node (ref "JP6") (pin "9") (pinfunction "9_9") (pintype "passive"))
      (node (ref "U$3") (pin "P$33") (pinfunction "33_P$33") (pintype "passive"))
    )
    (net (code "66") (name "/SOCK_NCS2") (class "Default")
      (node (ref "JP6") (pin "11") (pinfunction "11_11") (pintype "passive"))
      (node (ref "U$4") (pin "P$11") (pinfunction "11_P$11") (pintype "passive"))
    )
    (net (code "67") (name "/SOCK_NRD") (class "Default")
      (node (ref "JP6") (pin "7") (pinfunction "7_7") (pintype "passive"))
      (node (ref "U$3") (pin "P$11") (pinfunction "11_P$11") (pintype "passive"))
    )
    (net (code "68") (name "/SOCK_NRST") (class "Default")
      (node (ref "JP6") (pin "8") (pinfunction "8_8") (pintype "passive"))
      (node (ref "U$3") (pin "P$22") (pinfunction "22_P$22") (pintype "passive"))
    )
    (net (code "69") (name "/SOCK_NWR") (class "Default")
      (node (ref "JP6") (pin "13") (pinfunction "13_13") (pintype "passive"))
      (node (ref "U$4") (pin "P$33") (pinfunction "33_P$33") (pintype "passive"))
    )
    (net (code "70") (name "/SOCK_ROTA") (class "Default")
      (node (ref "JP6") (pin "2") (pinfunction "2_2") (pintype "passive"))
      (node (ref "U$1") (pin "P$11") (pinfunction "11_P$11") (pintype "passive"))
    )
    (net (code "71") (name "/SOCK_ROTB") (class "Default")
      (node (ref "JP6") (pin "4") (pinfunction "4_4") (pintype "passive"))
      (node (ref "U$1") (pin "P$33") (pinfunction "33_P$33") (pintype "passive"))
    )
    (net (code "72") (name "/SOCK_ROTSW") (class "Default")
      (node (ref "JP6") (pin "1") (pinfunction "1_1") (pintype "passive"))
      (node (ref "U$1") (pin "P$22") (pinfunction "22_P$22") (pintype "passive"))
    )
    (net (code "73") (name "/SOCK__SEL") (class "Default")
      (node (ref "JP6") (pin "3") (pinfunction "3_3") (pintype "passive"))
      (node (ref "U$1") (pin "P$44") (pinfunction "44_P$44") (pintype "passive"))
    )
    (net (code "74") (name "/SPI2_CLK") (class "Default")
      (node (ref "U$22") (pin "CLK") (pinfunction "CLK_CLK") (pintype "bidirectional"))
      (node (ref "U$23") (pin "34") (pinfunction "PB13_34") (pintype "bidirectional"))
    )
    (net (code "75") (name "/SPI2_MISO") (class "Default")
      (node (ref "U$22") (pin "DAT") (pinfunction "DAT_DAT") (pintype "bidirectional"))
      (node (ref "U$23") (pin "35") (pinfunction "PB14_35") (pintype "bidirectional"))
    )
    (net (code "76") (name "/SPI5_CLK") (class "Default")
      (node (ref "U$21") (pin "CLK") (pinfunction "CLK_CLK") (pintype "bidirectional"))
      (node (ref "U$23") (pin "26") (pinfunction "PB0_26") (pintype "bidirectional"))
    )
    (net (code "77") (name "/SPI5_MISO") (class "Default")
      (node (ref "U$21") (pin "DAT") (pinfunction "DAT_DAT") (pintype "bidirectional"))
      (node (ref "U$23") (pin "45") (pinfunction "PA12_45") (pintype "bidirectional"))
    )
    (net (code "78") (name "/SPI_CLK") (class "Default")
      (node (ref "JP5") (pin "2") (pinfunction "2_2") (pintype "passive"))
      (node (ref "U$2") (pin "P$2") (pinfunction "2_P$2") (pintype "passive"))
      (node (ref "U$23") (pin "21") (pinfunction "PA5_21") (pintype "bidirectional"))
      (node (ref "U$24") (pin "D5") (pinfunction "D5_D5") (pintype "bidirectional"))
      (node (ref "U$8") (pin "P$4") (pinfunction "4_P$4") (pintype "passive"))
      (node (ref "U$9") (pin "P$4") (pinfunction "4_P$4") (pintype "passive"))
    )
    (net (code "79") (name "/SPI_MISO") (class "Default")
      (node (ref "U$23") (pin "22") (pinfunction "PA6_22") (pintype "bidirectional"))
      (node (ref "U$24") (pin "D6") (pinfunction "D6_D6") (pintype "bidirectional"))
      (node (ref "U$8") (pin "P$3") (pinfunction "3_P$3") (pintype "passive"))
      (node (ref "U$9") (pin "P$3") (pinfunction "3_P$3") (pintype "passive"))
    )
    (net (code "80") (name "/SPI_MOSI") (class "Default")
      (node (ref "JP5") (pin "4") (pinfunction "4_4") (pintype "passive"))
      (node (ref "U$2") (pin "P$4") (pinfunction "4_P$4") (pintype "passive"))
      (node (ref "U$23") (pin "23") (pinfunction "PA7_23") (pintype "bidirectional"))
      (node (ref "U$24") (pin "D7") (pinfunction "D7_D7") (pintype "bidirectional"))
      (node (ref "U$8") (pin "P$2") (pinfunction "2_P$2") (pintype "passive"))
      (node (ref "U$9") (pin "P$2") (pinfunction "2_P$2") (pintype "passive"))
    )
    (net (code "81") (name "/SWCLK") (class "Default")
      (node (ref "SWD1") (pin "2") (pinfunction "2_2") (pintype "passive"))
      (node (ref "U$23") (pin "49") (pinfunction "PA14_49") (pintype "bidirectional"))
    )
    (net (code "82") (name "/SWDIO") (class "Default")
      (node (ref "SWD1") (pin "4") (pinfunction "4_4") (pintype "passive"))
      (node (ref "U$23") (pin "46") (pinfunction "PA13_46") (pintype "bidirectional"))
    )
    (net (code "83") (name "/SWO") (class "Default")
      (node (ref "SWD1") (pin "6") (pinfunction "6_6") (pintype "passive"))
      (node (ref "U$23") (pin "55") (pinfunction "PB3_55") (pintype "bidirectional"))
    )
    (net (code "84") (name "/USB12V") (class "Default")
      (node (ref "D1") (pin "A") (pinfunction "A_A") (pintype "passive"))
      (node (ref "D2") (pin "C") (pinfunction "C_C") (pintype "passive"))
      (node (ref "LM317") (pin "3") (pinfunction "3_3") (pintype "passive"))
      (node (ref "R1") (pin "2") (pinfunction "2_2") (pintype "passive"))
      (node (ref "SJ3") (pin "1") (pinfunction "1_1") (pintype "passive"))
      (node (ref "SJ5") (pin "2") (pinfunction "2_2") (pintype "passive"))
      (node (ref "SJ6") (pin "2") (pinfunction "2_2") (pintype "passive"))
    )
    (net (code "85") (name "/USBGND") (class "Default")
      (node (ref "C3") (pin "2") (pinfunction "2_2") (pintype "passive"))
      (node (ref "C4") (pin "2") (pinfunction "2_2") (pintype "passive"))
      (node (ref "JP1") (pin "10") (pinfunction "10_10") (pintype "passive"))
      (node (ref "JP1") (pin "5") (pinfunction "5_5") (pintype "passive"))
      (node (ref "JP1") (pin "6") (pinfunction "6_6") (pintype "passive"))
      (node (ref "JP2") (pin "1") (pinfunction "1_1") (pintype "passive"))
      (node (ref "JP2") (pin "3") (pinfunction "3_3") (pintype "passive"))
      (node (ref "JP2") (pin "5") (pinfunction "5_5") (pintype "passive"))
      (node (ref "R2") (pin "1") (pinfunction "A_1") (pintype "passive"))
      (node (ref "SJ4") (pin "1") (pinfunction "1_1") (pintype "passive"))
    )
    (net (code "86") (name "/USBVBUS") (class "Default")
      (node (ref "C3") (pin "1") (pinfunction "1_1") (pintype "passive"))
      (node (ref "D1") (pin "C") (pinfunction "C_C") (pintype "passive"))
      (node (ref "LM317") (pin "1") (pinfunction "1_1") (pintype "passive"))
      (node (ref "SJ12") (pin "1") (pinfunction "1_1") (pintype "passive"))
      (node (ref "SJ13") (pin "1") (pinfunction "1_1") (pintype "passive"))
      (node (ref "SJ14") (pin "1") (pinfunction "1_1") (pintype "passive"))
      (node (ref "SJ5") (pin "1") (pinfunction "1_1") (pintype "passive"))
      (node (ref "SJ6") (pin "1") (pinfunction "1_1") (pintype "passive"))
      (node (ref "SJ8") (pin "2") (pinfunction "2_2") (pintype "passive"))
      (node (ref "SJ9") (pin "2") (pinfunction "2_2") (pintype "passive"))
    )
    (net (code "87") (name "/V3.3") (class "Default")
      (node (ref "C1") (pin "1") (pinfunction "1_1") (pintype "passive"))
      (node (ref "C10") (pin "1") (pinfunction "1_1") (pintype "passive"))
      (node (ref "C11") (pin "1") (pinfunction "1_1") (pintype "passive"))
      (node (ref "C14") (pin "1") (pinfunction "1_1") (pintype "passive"))
      (node (ref "C15") (pin "1") (pinfunction "1_1") (pintype "passive"))
      (node (ref "C16") (pin "1") (pinfunction "1_1") (pintype "passive"))
      (node (ref "C6") (pin "1") (pinfunction "1_1") (pintype "passive"))
      (node (ref "C7") (pin "1") (pinfunction "1_1") (pintype "passive"))
      (node (ref "C8") (pin "1") (pinfunction "1_1") (pintype "passive"))
      (node (ref "JP6") (pin "14") (pinfunction "14_14") (pintype "passive"))
      (node (ref "JP6") (pin "5") (pinfunction "5_5") (pintype "passive"))
      (node (ref "JP7") (pin "1") (pinfunction "1_1") (pintype "passive"))
      (node (ref "JP8") (pin "1") (pinfunction "1_1") (pintype "passive"))
      (node (ref "R11") (pin "1") (pinfunction "1_1") (pintype "passive"))
      (node (ref "SJ10") (pin "2") (pinfunction "2_2") (pintype "passive"))
      (node (ref "SWD1") (pin "1") (pinfunction "1_1") (pintype "passive"))
      (node (ref "U$15") (pin "VOUT") (pinfunction "VO_VOUT") (pintype "output"))
      (node (ref "U$15") (pin "VOUTB") (pinfunction "BODY_VOUTB") (pintype "open_collector"))
      (node (ref "U$21") (pin "VCC") (pinfunction "VCC_VCC") (pintype "power_in"))
      (node (ref "U$22") (pin "VCC") (pinfunction "VCC_VCC") (pintype "power_in"))
      (node (ref "U$23") (pin "1") (pinfunction "1:VBAT_1") (pintype "bidirectional"))
      (node (ref "U$23") (pin "13") (pinfunction "13:VDDA_13") (pintype "bidirectional"))
      (node (ref "U$23") (pin "19") (pinfunction "19:VDD_19") (pintype "bidirectional"))
      (node (ref "U$23") (pin "32") (pinfunction "32:VDD_32") (pintype "bidirectional"))
      (node (ref "U$23") (pin "48") (pinfunction "48:VDD_48") (pintype "bidirectional"))
      (node (ref "U$23") (pin "64") (pinfunction "64:VDD_64") (pintype "bidirectional"))
      (node (ref "U$24") (pin "V3.3") (pinfunction "V3.3_V3.3") (pintype "bidirectional"))
      (node (ref "U$24") (pin "V3.3@1") (pinfunction "V3.3_V3.3@1") (pintype "bidirectional"))
      (node (ref "U$24") (pin "V3.3@2") (pinfunction "V3.3_V3.3@2") (pintype "bidirectional"))
      (node (ref "U1") (pin "23") (pinfunction "VCCB_2_23") (pintype "power_in"))
      (node (ref "U1") (pin "24") (pinfunction "VCCB_24") (pintype "power_in"))
    )
    (net (code "88") (name "/V5") (class "Default")
      (node (ref "C5") (pin "1") (pinfunction "1_1") (pintype "passive"))
      (node (ref "C9") (pin "1") (pinfunction "1_1") (pintype "passive"))
      (node (ref "JP6") (pin "20") (pinfunction "20_20") (pintype "passive"))
      (node (ref "JP6") (pin "21") (pinfunction "21_21") (pintype "passive"))
      (node (ref "JP6") (pin "30") (pinfunction "30_30") (pintype "passive"))
      (node (ref "JP7") (pin "9") (pinfunction "9_9") (pintype "passive"))
      (node (ref "JP8") (pin "9") (pinfunction "9_9") (pintype "passive"))
      (node (ref "SJ11") (pin "2") (pinfunction "2_2") (pintype "passive"))
      (node (ref "U$13") (pin "16") (pinfunction "VCC1_16") (pintype "bidirectional"))
      (node (ref "U$15") (pin "VIN") (pinfunction "VI_VIN") (pintype "input"))
      (node (ref "U$16") (pin "VO") (pinfunction "P$3_VO") (pintype "output"))
      (node (ref "U$24") (pin "V5") (pinfunction "V5_V5") (pintype "bidirectional"))
      (node (ref "U1") (pin "1") (pinfunction "VCCA_1") (pintype "power_in"))
    )
    (net (code "89") (name "/V12") (class "Default")
      (node (ref "C2") (pin "1") (pinfunction "1_1") (pintype "passive"))
      (node (ref "J2") (pin "3") (pinfunction "3_3") (pintype "passive"))
      (node (ref "SJ3") (pin "2") (pinfunction "2_2") (pintype "passive"))
      (node (ref "U$13") (pin "8") (pinfunction "VCC2_8") (pintype "bidirectional"))
      (node (ref "U$16") (pin "VI") (pinfunction "P$1_VI") (pintype "input"))
    )
    (net (code "90") (name "/VADJ") (class "Default")
      (node (ref "C4") (pin "1") (pinfunction "1_1") (pintype "passive"))
      (node (ref "D2") (pin "A") (pinfunction "A_A") (pintype "passive"))
      (node (ref "LM317") (pin "2") (pinfunction "2_2") (pintype "passive"))
      (node (ref "R1") (pin "1") (pinfunction "1_1") (pintype "passive"))
      (node (ref "R2") (pin "2") (pinfunction "S_2") (pintype "passive"))
    )
    (net (code "91") (name "/VBUS") (class "Default")
      (node (ref "JP2") (pin "2") (pinfunction "2_2") (pintype "passive"))
      (node (ref "JP2") (pin "4") (pinfunction "4_4") (pintype "passive"))
      (node (ref "SJ12") (pin "2") (pinfunction "2_2") (pintype "passive"))
    )
    (net (code "92") (name "/VBUS_A") (class "Default")
      (node (ref "JP1") (pin "4") (pinfunction "4_4") (pintype "passive"))
      (node (ref "SJ14") (pin "2") (pinfunction "2_2") (pintype "passive"))
    )
    (net (code "93") (name "/VCAP") (class "Default")
      (node (ref "C12") (pin "1") (pinfunction "1_1") (pintype "passive"))
      (node (ref "U$23") (pin "30") (pinfunction "30:VCAP_30") (pintype "bidirectional"))
    )
    (net (code "94") (name "/VCONN") (class "Default")
      (node (ref "JP2") (pin "6") (pinfunction "6_6") (pintype "passive"))
      (node (ref "SJ13") (pin "2") (pinfunction "2_2") (pintype "passive"))
    )
    (net (code "95") (name "/VCONNA") (class "Default")
      (node (ref "JP1") (pin "1") (pinfunction "1_1") (pintype "passive"))
      (node (ref "SJ9") (pin "1") (pinfunction "1_1") (pintype "passive"))
    )
    (net (code "96") (name "/VDD") (class "Default")
      (node (ref "JP1") (pin "12") (pinfunction "12_12") (pintype "passive"))
      (node (ref "SJ8") (pin "1") (pinfunction "1_1") (pintype "passive"))
    )
    (net (code "97") (name "/VLT_DIR") (class "Default")
      (node (ref "U$23") (pin "36") (pinfunction "PB15_36") (pintype "bidirectional"))
      (node (ref "U1") (pin "2") (pinfunction "DIR_2") (pintype "input"))
    )
    (net (code "98") (name "/VPU") (class "Default")
      (node (ref "JP1") (pin "11") (pinfunction "11_11") (pintype "passive"))
    )
    (net (code "99") (name "/V_PULLUP") (class "Default")
      (node (ref "JP1") (pin "2") (pinfunction "2_2") (pintype "passive"))
    )
    (net (code "100") (name "/WIFI_CS") (class "Default")
      (node (ref "U$23") (pin "28") (pinfunction "PB2_28") (pintype "bidirectional"))
      (node (ref "U$24") (pin "D8") (pinfunction "D8_D8") (pintype "bidirectional"))
    )
    (net (code "101") (name "/WIFI_GPIO") (class "Default")
      (node (ref "U$24") (pin "D1") (pinfunction "D1_D1") (pintype "bidirectional"))
    )
    (net (code "102") (name "/WIFI_IRQ") (class "Default")
      (node (ref "U$23") (pin "29") (pinfunction "PB10_29") (pintype "bidirectional"))
      (node (ref "U$24") (pin "D0") (pinfunction "D0_D0") (pintype "bidirectional"))
    )
    (net (code "103") (name "Net-(R4-Pad1)") (class "Default")
      (node (ref "R4") (pin "1") (pinfunction "1_1") (pintype "passive"))
      (node (ref "R5") (pin "2") (pinfunction "2_2") (pintype "passive"))
      (node (ref "U$18") (pin "E") (pinfunction "E_E") (pintype "bidirectional"))
    )
    (net (code "104") (name "Net-(R6-Pad1)") (class "Default")
      (node (ref "R6") (pin "1") (pinfunction "1_1") (pintype "passive"))
      (node (ref "U$19") (pin "D") (pinfunction "D_D") (pintype "bidirectional"))
    )
    (net (code "105") (name "Net-(R6-Pad2)") (class "Default")
      (node (ref "R6") (pin "2") (pinfunction "2_2") (pintype "passive"))
      (node (ref "U$18") (pin "CATH") (pinfunction "CATH_CATH") (pintype "bidirectional"))
    )
    (net (code "106") (name "Net-(U$2-11)") (class "Default")
      (node (ref "JP6") (pin "15") (pinfunction "15_15") (pintype "passive"))
      (node (ref "U$2") (pin "P$11") (pinfunction "11_P$11") (pintype "passive"))
    )
    (net (code "107") (name "Net-(U$2-22)") (class "Default")
      (node (ref "JP6") (pin "16") (pinfunction "16_16") (pintype "passive"))
      (node (ref "U$2") (pin "P$22") (pinfunction "22_P$22") (pintype "passive"))
    )
    (net (code "108") (name "Net-(U$2-33)") (class "Default")
      (node (ref "JP6") (pin "17") (pinfunction "17_17") (pintype "passive"))
      (node (ref "U$2") (pin "P$33") (pinfunction "33_P$33") (pintype "passive"))
    )
    (net (code "109") (name "Net-(U$2-44)") (class "Default")
      (node (ref "JP6") (pin "18") (pinfunction "18_18") (pintype "passive"))
      (node (ref "U$2") (pin "P$44") (pinfunction "44_P$44") (pintype "passive"))
    )
    (net (code "110") (name "Net-(U$6-11)") (class "Default")
      (node (ref "JP6") (pin "23") (pinfunction "23_23") (pintype "passive"))
      (node (ref "U$6") (pin "P$11") (pinfunction "11_P$11") (pintype "passive"))
    )
    (net (code "111") (name "Net-(U$6-22)") (class "Default")
      (node (ref "JP6") (pin "24") (pinfunction "24_24") (pintype "passive"))
      (node (ref "U$6") (pin "P$22") (pinfunction "22_P$22") (pintype "passive"))
    )
    (net (code "112") (name "Net-(U$6-33)") (class "Default")
      (node (ref "JP6") (pin "26") (pinfunction "26_26") (pintype "passive"))
      (node (ref "U$6") (pin "P$33") (pinfunction "33_P$33") (pintype "passive"))
    )
    (net (code "113") (name "Net-(U$7-11)") (class "Default")
      (node (ref "JP6") (pin "25") (pinfunction "25_25") (pintype "passive"))
      (node (ref "U$7") (pin "P$11") (pinfunction "11_P$11") (pintype "passive"))
    )
    (net (code "114") (name "Net-(U$7-22)") (class "Default")
      (node (ref "JP6") (pin "28") (pinfunction "28_28") (pintype "passive"))
      (node (ref "U$7") (pin "P$22") (pinfunction "22_P$22") (pintype "passive"))
    )
    (net (code "115") (name "Net-(U$7-33)") (class "Default")
      (node (ref "JP6") (pin "27") (pinfunction "27_27") (pintype "passive"))
      (node (ref "U$7") (pin "P$33") (pinfunction "33_P$33") (pintype "passive"))
    )
    (net (code "116") (name "Net-(U$8-11)") (class "Default")
      (node (ref "JP8") (pin "5") (pinfunction "5_5") (pintype "passive"))
      (node (ref "U$8") (pin "P$11") (pinfunction "11_P$11") (pintype "passive"))
    )
    (net (code "117") (name "Net-(U$8-22)") (class "Default")
      (node (ref "JP8") (pin "4") (pinfunction "4_4") (pintype "passive"))
      (node (ref "U$8") (pin "P$22") (pinfunction "22_P$22") (pintype "passive"))
    )
    (net (code "118") (name "Net-(U$8-33)") (class "Default")
      (node (ref "JP8") (pin "3") (pinfunction "3_3") (pintype "passive"))
      (node (ref "U$8") (pin "P$33") (pinfunction "33_P$33") (pintype "passive"))
    )
    (net (code "119") (name "Net-(U$8-44)") (class "Default")
      (node (ref "JP8") (pin "2") (pinfunction "2_2") (pintype "passive"))
      (node (ref "U$8") (pin "P$44") (pinfunction "44_P$44") (pintype "passive"))
    )
    (net (code "120") (name "Net-(U$9-11)") (class "Default")
      (node (ref "JP7") (pin "5") (pinfunction "5_5") (pintype "passive"))
      (node (ref "U$9") (pin "P$11") (pinfunction "11_P$11") (pintype "passive"))
    )
    (net (code "121") (name "Net-(U$9-22)") (class "Default")
      (node (ref "JP7") (pin "4") (pinfunction "4_4") (pintype "passive"))
      (node (ref "U$9") (pin "P$22") (pinfunction "22_P$22") (pintype "passive"))
    )
    (net (code "122") (name "Net-(U$9-33)") (class "Default")
      (node (ref "JP7") (pin "3") (pinfunction "3_3") (pintype "passive"))
      (node (ref "U$9") (pin "P$33") (pinfunction "33_P$33") (pintype "passive"))
    )
    (net (code "123") (name "Net-(U$9-44)") (class "Default")
      (node (ref "JP7") (pin "2") (pinfunction "2_2") (pintype "passive"))
      (node (ref "U$9") (pin "P$44") (pinfunction "44_P$44") (pintype "passive"))
    )
    (net (code "124") (name "Net-(U$10-33)") (class "Default")
      (node (ref "JP7") (pin "7") (pinfunction "7_7") (pintype "passive"))
      (node (ref "U$10") (pin "P$33") (pinfunction "33_P$33") (pintype "passive"))
    )
    (net (code "125") (name "Net-(U$10-44)") (class "Default")
      (node (ref "JP7") (pin "6") (pinfunction "6_6") (pintype "passive"))
      (node (ref "U$10") (pin "P$44") (pinfunction "44_P$44") (pintype "passive"))
    )
    (net (code "126") (name "Net-(U$11-33)") (class "Default")
      (node (ref "JP8") (pin "7") (pinfunction "7_7") (pintype "passive"))
      (node (ref "U$11") (pin "P$33") (pinfunction "33_P$33") (pintype "passive"))
    )
    (net (code "127") (name "Net-(U$11-44)") (class "Default")
      (node (ref "JP8") (pin "6") (pinfunction "6_6") (pintype "passive"))
      (node (ref "U$11") (pin "P$44") (pinfunction "44_P$44") (pintype "passive"))
    )
    (net (code "128") (name "Net-(U$23-PH1)") (class "Default")
      (node (ref "R3") (pin "2") (pinfunction "2_2") (pintype "passive"))
      (node (ref "U$23") (pin "6") (pinfunction "PH1_6") (pintype "bidirectional"))
    )
    (net (code "129") (name "unconnected-(JP1-Pad3)") (class "Default")
      (node (ref "JP1") (pin "3") (pinfunction "3_3") (pintype "passive"))
    )
    (net (code "130") (name "unconnected-(JP6-Pad29)") (class "Default")
      (node (ref "JP6") (pin "29") (pinfunction "29_29") (pintype "passive"))
    )
    (net (code "131") (name "unconnected-(R2-E-Pad3)") (class "Default")
      (node (ref "R2") (pin "3") (pinfunction "E_3") (pintype "passive"))
    )
    (net (code "132") (name "unconnected-(U$4-4-PadP$4)") (class "Default")
      (node (ref "U$4") (pin "P$4") (pinfunction "4_P$4") (pintype "passive"))
    )
    (net (code "133") (name "unconnected-(U$4-44-PadP$44)") (class "Default")
      (node (ref "U$4") (pin "P$44") (pinfunction "44_P$44") (pintype "passive"))
    )
    (net (code "134") (name "unconnected-(U$6-4-PadP$4)") (class "Default")
      (node (ref "U$6") (pin "P$4") (pinfunction "4_P$4") (pintype "passive"))
    )
    (net (code "135") (name "unconnected-(U$6-44-PadP$44)") (class "Default")
      (node (ref "U$6") (pin "P$44") (pinfunction "44_P$44") (pintype "passive"))
    )
    (net (code "136") (name "unconnected-(U$7-4-PadP$4)") (class "Default")
      (node (ref "U$7") (pin "P$4") (pinfunction "4_P$4") (pintype "passive"))
    )
    (net (code "137") (name "unconnected-(U$7-44-PadP$44)") (class "Default")
      (node (ref "U$7") (pin "P$44") (pinfunction "44_P$44") (pintype "passive"))
    )
    (net (code "138") (name "unconnected-(U$10-1-PadP$1)") (class "Default")
      (node (ref "U$10") (pin "P$1") (pinfunction "1_P$1") (pintype "passive"))
    )
    (net (code "139") (name "unconnected-(U$10-2-PadP$2)") (class "Default")
      (node (ref "U$10") (pin "P$2") (pinfunction "2_P$2") (pintype "passive"))
    )
    (net (code "140") (name "unconnected-(U$10-11-PadP$11)") (class "Default")
      (node (ref "U$10") (pin "P$11") (pinfunction "11_P$11") (pintype "passive"))
    )
    (net (code "141") (name "unconnected-(U$10-22-PadP$22)") (class "Default")
      (node (ref "U$10") (pin "P$22") (pinfunction "22_P$22") (pintype "passive"))
    )
    (net (code "142") (name "unconnected-(U$11-1-PadP$1)") (class "Default")
      (node (ref "U$11") (pin "P$1") (pinfunction "1_P$1") (pintype "passive"))
    )
    (net (code "143") (name "unconnected-(U$11-2-PadP$2)") (class "Default")
      (node (ref "U$11") (pin "P$2") (pinfunction "2_P$2") (pintype "passive"))
    )
    (net (code "144") (name "unconnected-(U$11-11-PadP$11)") (class "Default")
      (node (ref "U$11") (pin "P$11") (pinfunction "11_P$11") (pintype "passive"))
    )
    (net (code "145") (name "unconnected-(U$11-22-PadP$22)") (class "Default")
      (node (ref "U$11") (pin "P$22") (pinfunction "22_P$22") (pintype "passive"))
    )
    (net (code "146") (name "unconnected-(U$12-AN-PadANODE)") (class "Default")
      (node (ref "U$12") (pin "ANODE") (pinfunction "AN_ANODE") (pintype "input"))
    )
    (net (code "147") (name "unconnected-(U$12-CA-PadCATHODE)") (class "Default")
      (node (ref "U$12") (pin "CATHODE") (pinfunction "CA_CATHODE") (pintype "output"))
    )
    (net (code "148") (name "unconnected-(U$24-PadA0)") (class "Default")
      (node (ref "U$24") (pin "A0") (pinfunction "A0_A0") (pintype "bidirectional"))
    )
    (net (code "149") (name "unconnected-(U$24-PadCLK)") (class "Default")
      (node (ref "U$24") (pin "CLK") (pinfunction "CLK_CLK") (pintype "bidirectional"))
    )
    (net (code "150") (name "unconnected-(U$24-PadCMD)") (class "Default")
      (node (ref "U$24") (pin "CMD") (pinfunction "CMD_CMD") (pintype "bidirectional"))
    )
    (net (code "151") (name "unconnected-(U$24-PadD2)") (class "Default")
      (node (ref "U$24") (pin "D2") (pinfunction "D2_D2") (pintype "bidirectional"))
    )
    (net (code "152") (name "unconnected-(U$24-PadD3)") (class "Default")
      (node (ref "U$24") (pin "D3") (pinfunction "D3_D3") (pintype "bidirectional"))
    )
    (net (code "153") (name "unconnected-(U$24-PadD4)") (class "Default")
      (node (ref "U$24") (pin "D4") (pinfunction "D4_D4") (pintype "bidirectional"))
    )
    (net (code "154") (name "unconnected-(U$24-PadEN)") (class "Default")
      (node (ref "U$24") (pin "EN") (pinfunction "EN_EN") (pintype "bidirectional"))
    )
    (net (code "155") (name "unconnected-(U$24-PadRST)") (class "Default")
      (node (ref "U$24") (pin "RST") (pinfunction "RST_RST") (pintype "bidirectional"))
    )
    (net (code "156") (name "unconnected-(U$24-PadRSV)") (class "Default")
      (node (ref "U$24") (pin "RSV") (pinfunction "RSV_RSV") (pintype "bidirectional"))
    )
    (net (code "157") (name "unconnected-(U$24-PadRX)") (class "Default")
      (node (ref "U$24") (pin "RX") (pinfunction "RX_RX") (pintype "bidirectional"))
    )
    (net (code "158") (name "unconnected-(U$24-PadSD0)") (class "Default")
      (node (ref "U$24") (pin "SD0") (pinfunction "SD0_SD0") (pintype "bidirectional"))
    )
    (net (code "159") (name "unconnected-(U$24-PadSD1)") (class "Default")
      (node (ref "U$24") (pin "SD1") (pinfunction "SD1_SD1") (pintype "bidirectional"))
    )
    (net (code "160") (name "unconnected-(U$24-PadSD2)") (class "Default")
      (node (ref "U$24") (pin "SD2") (pinfunction "SD2_SD2") (pintype "bidirectional"))
    )
    (net (code "161") (name "unconnected-(U$24-PadSD3)") (class "Default")
      (node (ref "U$24") (pin "SD3") (pinfunction "SD3_SD3") (pintype "bidirectional"))
    )
    (net (code "162") (name "unconnected-(U$24-PadTX)") (class "Default")
      (node (ref "U$24") (pin "TX") (pinfunction "TX_TX") (pintype "bidirectional"))
    )
    (net (code "163") (name "unconnected-(U$24-RSV-PadRSV@1)") (class "Default")
      (node (ref "U$24") (pin "RSV@1") (pinfunction "RSV_RSV@1") (pintype "bidirectional"))
    )
    (net (code "164") (name "unconnected-(U1-A6-Pad9)") (class "Default")
      (node (ref "U1") (pin "9") (pinfunction "A6_9") (pintype "bidirectional"))
    )
    (net (code "165") (name "unconnected-(U1-A7-Pad10)") (class "Default")
      (node (ref "U1") (pin "10") (pinfunction "A7_10") (pintype "bidirectional"))
    )
    (net (code "166") (name "unconnected-(U1-B6-Pad15)") (class "Default")
      (node (ref "U1") (pin "15") (pinfunction "B6_15") (pintype "bidirectional"))
    )
    (net (code "167") (name "unconnected-(U1-B7-Pad14)") (class "Default")
      (node (ref "U1") (pin "14") (pinfunction "B7_14") (pintype "bidirectional"))
    )
  )
)
